# AFE_BQ-Chip.net
KiCad netlist of a schematic drawn in Altium Designer
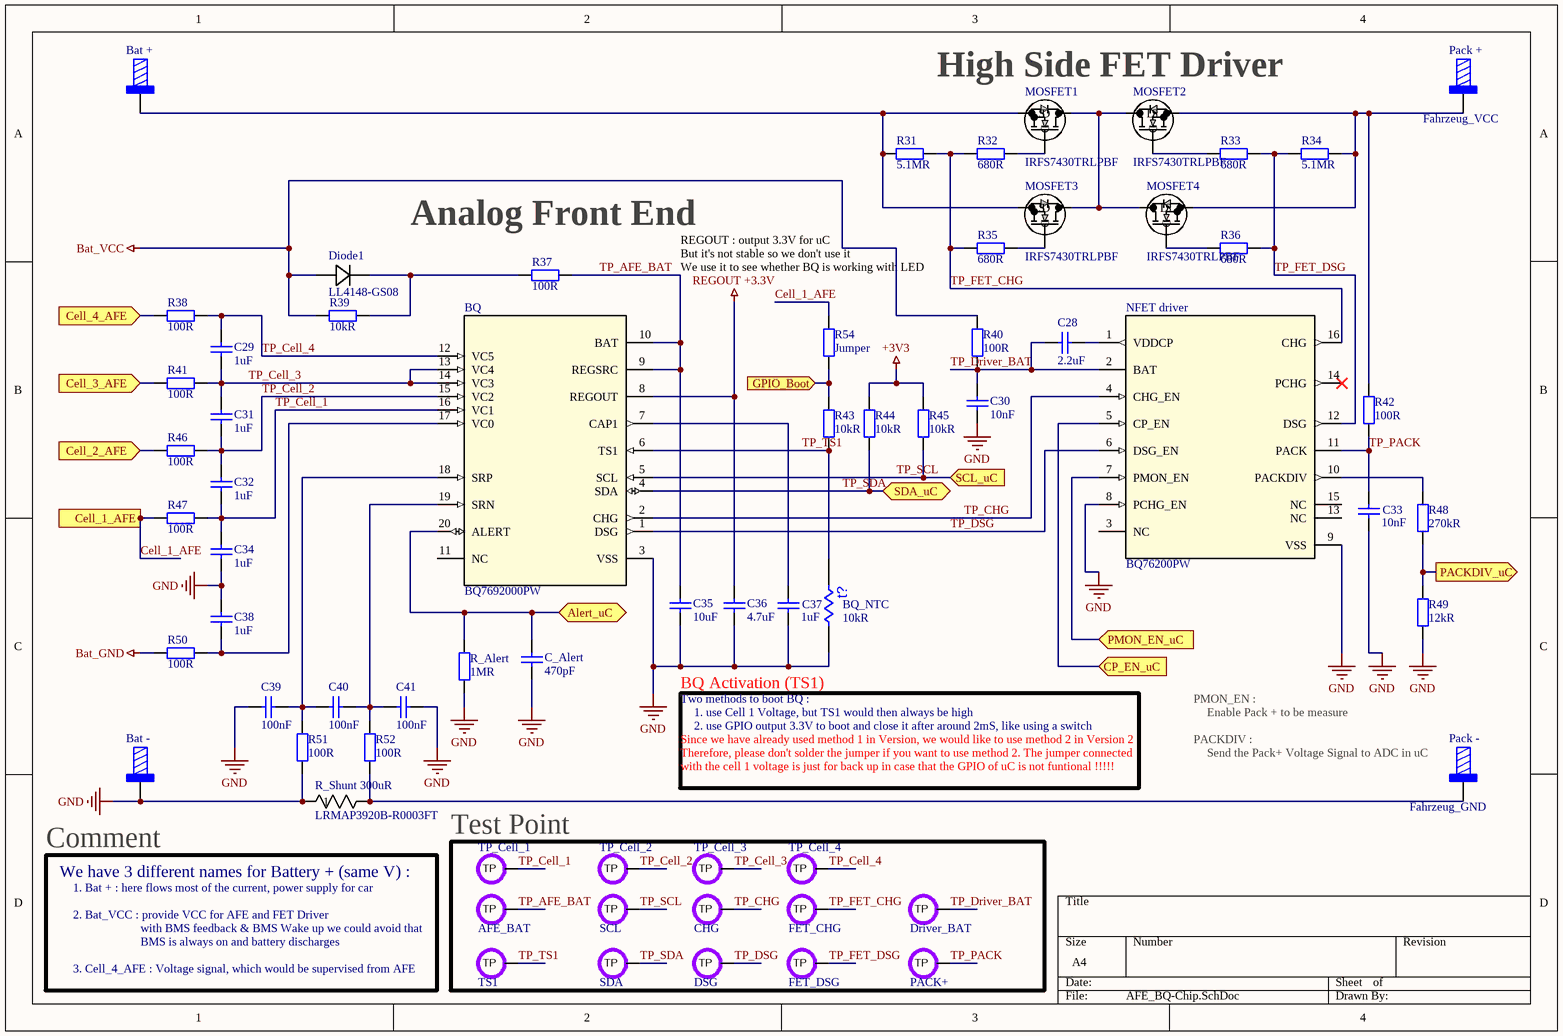
[diagram p0: AFE_BQ-Chip.SchDoc]

(export (version "E")
  (design (tool "Eeschema 10.0.6"))
  (components
    (comp (ref "AFE_BAT")
      (value "TP_1")
      (footprint "Test point")
      (libsource (lib "Schlib1") (part "Test point"))
    )
    (comp (ref "Bat +")
      (value "M4x6mm")
      (footprint "7461096_for chemical surfaces")
      (description "WP-SHFU Press-Fit with External thread, full plain, 7x7mm, 9 pins, M4x6mm, 130A")
      (fields (field (name "PART NUMBER") "7461096") (field (name "PUBLISHER") "Wurth Elektronik"))
      (libsource (lib "GND Pillar") (part "7461096"))
    )
    (comp (ref "Bat -")
      (value "M4x6mm")
      (footprint "7461096_for chemical surfaces")
      (description "WP-SHFU Press-Fit with External thread, full plain, 7x7mm, 9 pins, M4x6mm, 130A")
      (fields (field (name "PART NUMBER") "7461096") (field (name "PUBLISHER") "Wurth Elektronik"))
      (libsource (lib "GND Pillar") (part "7461096"))
    )
    (comp (ref "BQ")
      (value "BQ7692000PW")
      (footprint "PW0020A_N")
      (description "AFE Cell battery monitor")
      (fields
        (field (name "PARTNUMBER") "BQ7692000PWR")
        (field (name "MANUFACTURER") "Texas Instruments")
        (field (name "COPYRIGHT") "Copyright (C) 2018 Accelerated Designs. All rights reserved")
      )
      (libsource (lib "BQ7692000PW") (part "BQ7692000PW"))
    )
    (comp (ref "BQ_NTC")
      (value "10kR")
      (footprint "J1-0603")
      (description "Thermistor")
      (fields (field (name "PUBLISHER") "Altium Limited"))
      (libsource (lib "Miscellaneous Devices") (part "Res Thermal"))
    )
    (comp (ref "C28")
      (value "2.2uF")
      (footprint "1608[0603]")
      (description "Capacitor")
      (fields (field (name "PUBLISHER") "Altium Limited"))
      (libsource (lib "Miscellaneous Devices") (part "Cap"))
    )
    (comp (ref "C29")
      (value "1uF")
      (footprint "1608[0603]")
      (description "Capacitor")
      (fields (field (name "PUBLISHER") "Altium Limited"))
      (libsource (lib "Miscellaneous Devices") (part "Cap"))
    )
    (comp (ref "C30")
      (value "10nF")
      (footprint "1608[0603]")
      (description "Capacitor")
      (fields (field (name "PUBLISHER") "Altium Limited"))
      (libsource (lib "Miscellaneous Devices") (part "Cap"))
    )
    (comp (ref "C31")
      (value "1uF")
      (footprint "1608[0603]")
      (description "Capacitor")
      (fields (field (name "PUBLISHER") "Altium Limited"))
      (libsource (lib "Miscellaneous Devices") (part "Cap"))
    )
    (comp (ref "C32")
      (value "1uF")
      (footprint "1608[0603]")
      (description "Capacitor")
      (fields (field (name "PUBLISHER") "Altium Limited"))
      (libsource (lib "Miscellaneous Devices") (part "Cap"))
    )
    (comp (ref "C33")
      (value "10nF")
      (footprint "1608[0603]")
      (description "Capacitor")
      (fields (field (name "PUBLISHER") "Altium Limited"))
      (libsource (lib "Miscellaneous Devices") (part "Cap"))
    )
    (comp (ref "C34")
      (value "1uF")
      (footprint "1608[0603]")
      (description "Capacitor")
      (fields (field (name "PUBLISHER") "Altium Limited"))
      (libsource (lib "Miscellaneous Devices") (part "Cap"))
    )
    (comp (ref "C35")
      (value "10uF")
      (footprint "1608[0603]")
      (description "Capacitor")
      (fields (field (name "PUBLISHER") "Altium Limited"))
      (libsource (lib "Miscellaneous Devices") (part "Cap"))
    )
    (comp (ref "C36")
      (value "4.7uF")
      (footprint "1608[0603]")
      (description "Capacitor")
      (fields (field (name "PUBLISHER") "Altium Limited"))
      (libsource (lib "Miscellaneous Devices") (part "Cap"))
    )
    (comp (ref "C37")
      (value "1uF")
      (footprint "1608[0603]")
      (description "Capacitor")
      (fields (field (name "PUBLISHER") "Altium Limited"))
      (libsource (lib "Miscellaneous Devices") (part "Cap"))
    )
    (comp (ref "C38")
      (value "1uF")
      (footprint "1608[0603]")
      (description "Capacitor")
      (fields (field (name "PUBLISHER") "Altium Limited"))
      (libsource (lib "Miscellaneous Devices") (part "Cap"))
    )
    (comp (ref "C39")
      (value "100nF")
      (footprint "1608[0603]")
      (description "Capacitor")
      (fields (field (name "PUBLISHER") "Altium Limited"))
      (libsource (lib "Miscellaneous Devices") (part "Cap"))
    )
    (comp (ref "C40")
      (value "100nF")
      (footprint "1608[0603]")
      (description "Capacitor")
      (fields (field (name "PUBLISHER") "Altium Limited"))
      (libsource (lib "Miscellaneous Devices") (part "Cap"))
    )
    (comp (ref "C41")
      (value "100nF")
      (footprint "1608[0603]")
      (description "Capacitor")
      (fields (field (name "PUBLISHER") "Altium Limited"))
      (libsource (lib "Miscellaneous Devices") (part "Cap"))
    )
    (comp (ref "CHG") (value "TP_1") (footprint "Test point") (libsource (lib "Schlib1") (part "Test point")))
    (comp (ref "C_Alert")
      (value "470pF")
      (footprint "1608[0603]")
      (description "Capacitor")
      (fields (field (name "PUBLISHER") "Altium Limited"))
      (libsource (lib "Miscellaneous Devices") (part "Cap"))
    )
    (comp (ref "Diode1")
      (value "LL4148-GS08")
      (footprint "MELF_SOD-80_VIS")
      (description "No Description Available")
      (fields (field (name "COPYRIGHT") "Copyright (C) 2018 Accelerated Designs. All rights reserved"))
      (libsource (lib "Small Signal Switching Diodes") (part "LL4148-GS08"))
    )
    (comp (ref "Driver_BAT")
      (value "TP_1")
      (footprint "Test point")
      (libsource (lib "Schlib1") (part "Test point"))
    )
    (comp (ref "DSG") (value "TP_1") (footprint "Test point") (libsource (lib "Schlib1") (part "Test point")))
    (comp (ref "FET_CHG")
      (value "TP_1")
      (footprint "Test point")
      (libsource (lib "Schlib1") (part "Test point"))
    )
    (comp (ref "FET_DSG")
      (value "TP_1")
      (footprint "Test point")
      (libsource (lib "Schlib1") (part "Test point"))
    )
    (comp (ref "MOSFET1")
      (value "IRFS7430TRLPBF")
      (footprint "D2PAK_TO-263AB_INF-M")
      (description "No Description Available")
      (fields (field (name "COPYRIGHT") "Copyright (C) 2018 Accelerated Designs. All rights reserved"))
      (libsource (lib "Power MOSFET") (part "IRFS7430TRLPBF"))
    )
    (comp (ref "MOSFET2")
      (value "IRFS7430TRLPBF")
      (footprint "D2PAK_TO-263AB_INF-M")
      (description "No Description Available")
      (fields (field (name "COPYRIGHT") "Copyright (C) 2018 Accelerated Designs. All rights reserved"))
      (libsource (lib "Power MOSFET") (part "IRFS7430TRLPBF"))
    )
    (comp (ref "MOSFET3")
      (value "IRFS7430TRLPBF")
      (footprint "D2PAK_TO-263AB_INF-M")
      (description "No Description Available")
      (fields (field (name "COPYRIGHT") "Copyright (C) 2018 Accelerated Designs. All rights reserved"))
      (libsource (lib "Power MOSFET") (part "IRFS7430TRLPBF"))
    )
    (comp (ref "MOSFET4")
      (value "IRFS7430TRLPBF")
      (footprint "D2PAK_TO-263AB_INF-M")
      (description "No Description Available")
      (fields (field (name "COPYRIGHT") "Copyright (C) 2018 Accelerated Designs. All rights reserved"))
      (libsource (lib "Power MOSFET") (part "IRFS7430TRLPBF"))
    )
    (comp (ref "NFET driver")
      (value "BQ76200PW")
      (footprint "PW0016A_L")
      (description "high-side NFET driver")
      (fields
        (field (name "PARTNUMBER") "BQ76200PWR")
        (field (name "MANUFACTURER") "Texas Instruments")
        (field (name "COPYRIGHT") "Copyright (C) 2018 Accelerated Designs. All rights reserved")
      )
      (libsource (lib "BQ76200PW") (part "BQ76200PW"))
    )
    (comp (ref "Pack +")
      (value "Fahrzeug_VCC")
      (footprint "7461096_for chemical surfaces")
      (description "WP-SHFU Press-Fit with External thread, full plain, 7x7mm, 9 pins, M4x6mm, 130A")
      (fields (field (name "PART NUMBER") "7461096") (field (name "PUBLISHER") "Wurth Elektronik"))
      (libsource (lib "GND Pillar") (part "7461096"))
    )
    (comp (ref "Pack -")
      (value "Fahrzeug_GND")
      (footprint "7461096_for chemical surfaces")
      (description "WP-SHFU Press-Fit with External thread, full plain, 7x7mm, 9 pins, M4x6mm, 130A")
      (fields (field (name "PART NUMBER") "7461096") (field (name "PUBLISHER") "Wurth Elektronik"))
      (libsource (lib "GND Pillar") (part "7461096"))
    )
    (comp (ref "PACK+")
      (value "TP_1")
      (footprint "Test point")
      (libsource (lib "Schlib1") (part "Test point"))
    )
    (comp (ref "R31")
      (value "5.1MR")
      (footprint "J1-0603")
      (description "Resistor")
      (fields (field (name "PUBLISHER") "Altium Limited"))
      (libsource (lib "") (part "Res2_3"))
    )
    (comp (ref "R32")
      (value "680R")
      (footprint "J1-0603")
      (description "Resistor")
      (fields (field (name "PUBLISHER") "Altium Limited"))
      (libsource (lib "") (part "Res2_3"))
    )
    (comp (ref "R33")
      (value "680R")
      (footprint "J1-0603")
      (description "Resistor")
      (fields (field (name "PUBLISHER") "Altium Limited"))
      (libsource (lib "") (part "Res2_3"))
    )
    (comp (ref "R34")
      (value "5.1MR")
      (footprint "J1-0603")
      (description "Resistor")
      (fields (field (name "PUBLISHER") "Altium Limited"))
      (libsource (lib "") (part "Res2_3"))
    )
    (comp (ref "R35")
      (value "680R")
      (footprint "J1-0603")
      (description "Resistor")
      (fields (field (name "PUBLISHER") "Altium Limited"))
      (libsource (lib "") (part "Res2_3"))
    )
    (comp (ref "R36")
      (value "680R")
      (footprint "J1-0603")
      (description "Resistor")
      (fields (field (name "PUBLISHER") "Altium Limited"))
      (libsource (lib "") (part "Res2_3"))
    )
    (comp (ref "R37")
      (value "100R")
      (footprint "J1-0603")
      (description "Resistor")
      (fields (field (name "PUBLISHER") "Altium Limited"))
      (libsource (lib "Miscellaneous Devices") (part "Res2"))
    )
    (comp (ref "R38")
      (value "100R")
      (footprint "J1-0603")
      (description "Resistor")
      (fields (field (name "PUBLISHER") "Altium Limited"))
      (libsource (lib "Miscellaneous Devices") (part "Res2"))
    )
    (comp (ref "R39")
      (value "10kR")
      (footprint "J1-0603")
      (description "Resistor")
      (fields (field (name "PUBLISHER") "Altium Limited"))
      (libsource (lib "Miscellaneous Devices") (part "Res2"))
    )
    (comp (ref "R40")
      (value "100R")
      (footprint "J1-0603")
      (description "Resistor")
      (fields (field (name "PUBLISHER") "Altium Limited"))
      (libsource (lib "") (part "Res2_1"))
    )
    (comp (ref "R41")
      (value "100R")
      (footprint "J1-0603")
      (description "Resistor")
      (fields (field (name "PUBLISHER") "Altium Limited"))
      (libsource (lib "Miscellaneous Devices") (part "Res2"))
    )
    (comp (ref "R42")
      (value "100R")
      (footprint "J1-0603")
      (description "Resistor")
      (fields (field (name "PUBLISHER") "Altium Limited"))
      (libsource (lib "") (part "Res2_2"))
    )
    (comp (ref "R43")
      (value "10kR")
      (footprint "J1-0603")
      (description "Resistor")
      (fields (field (name "PUBLISHER") "Altium Limited"))
      (libsource (lib "Miscellaneous Devices") (part "Res2"))
    )
    (comp (ref "R44")
      (value "10kR")
      (footprint "J1-0603")
      (description "Resistor")
      (fields (field (name "PUBLISHER") "Altium Limited"))
      (libsource (lib "") (part "Res2_1"))
    )
    (comp (ref "R45")
      (value "10kR")
      (footprint "J1-0603")
      (description "Resistor")
      (fields (field (name "PUBLISHER") "Altium Limited"))
      (libsource (lib "") (part "Res2_1"))
    )
    (comp (ref "R46")
      (value "100R")
      (footprint "J1-0603")
      (description "Resistor")
      (fields (field (name "PUBLISHER") "Altium Limited"))
      (libsource (lib "Miscellaneous Devices") (part "Res2"))
    )
    (comp (ref "R47")
      (value "100R")
      (footprint "J1-0603")
      (description "Resistor")
      (fields (field (name "PUBLISHER") "Altium Limited"))
      (libsource (lib "Miscellaneous Devices") (part "Res2"))
    )
    (comp (ref "R48")
      (value "270kR")
      (footprint "J1-0603")
      (description "Resistor")
      (fields (field (name "PUBLISHER") "Altium Limited"))
      (libsource (lib "") (part "Res2_2"))
    )
    (comp (ref "R49")
      (value "12kR")
      (footprint "J1-0603")
      (description "Resistor")
      (fields (field (name "PUBLISHER") "Altium Limited"))
      (libsource (lib "") (part "Res2_2"))
    )
    (comp (ref "R50")
      (value "100R")
      (footprint "J1-0603")
      (description "Resistor")
      (fields (field (name "PUBLISHER") "Altium Limited"))
      (libsource (lib "") (part "Res2_1"))
    )
    (comp (ref "R51")
      (value "100R")
      (footprint "J1-0603")
      (description "Resistor")
      (fields (field (name "PUBLISHER") "Altium Limited"))
      (libsource (lib "Miscellaneous Devices") (part "Res2"))
    )
    (comp (ref "R52")
      (value "100R")
      (footprint "J1-0603")
      (description "Resistor")
      (fields (field (name "PUBLISHER") "Altium Limited"))
      (libsource (lib "Miscellaneous Devices") (part "Res2"))
    )
    (comp (ref "R54")
      (value "Jumper")
      (footprint "J1-0603")
      (description "Resistor")
      (fields (field (name "PUBLISHER") "Altium Limited"))
      (libsource (lib "") (part "Res2_2"))
    )
    (comp (ref "R_Alert")
      (value "1MR")
      (footprint "J1-0603")
      (description "Resistor")
      (fields (field (name "PUBLISHER") "Altium Limited"))
      (libsource (lib "Miscellaneous Devices") (part "Res2"))
    )
    (comp (ref "R_Shunt 300uR")
      (value "LRMAP3920B-R0003FT")
      (footprint "RES_LRMAP3920B-R0003FT_WEL")
      (description "No Description Available")
      (fields (field (name "COPYRIGHT") "Copyright (C) 2018 Accelerated Designs. All rights reserved"))
      (libsource (lib "Shunt R") (part "LRMAP3920B-R0003FT"))
    )
    (comp (ref "SCL") (value "TP_1") (footprint "Test point") (libsource (lib "Schlib1") (part "Test point")))
    (comp (ref "SDA") (value "TP_1") (footprint "Test point") (libsource (lib "Schlib1") (part "Test point")))
    (comp (ref "TP_Cell_1")
      (value "TP_1")
      (footprint "Test point")
      (libsource (lib "Schlib1") (part "Test point"))
    )
    (comp (ref "TP_Cell_2")
      (value "TP_1")
      (footprint "Test point")
      (libsource (lib "Schlib1") (part "Test point"))
    )
    (comp (ref "TP_Cell_3")
      (value "TP_1")
      (footprint "Test point")
      (libsource (lib "Schlib1") (part "Test point"))
    )
    (comp (ref "TP_Cell_4")
      (value "TP_1")
      (footprint "Test point")
      (libsource (lib "Schlib1") (part "Test point"))
    )
    (comp (ref "TS1") (value "TP_1") (footprint "Test point") (libsource (lib "Schlib1") (part "Test point")))
  )
  (nets
    (net (code "1") (name "+3V3") (class "Default")
      (node (ref "R44") (pin "1") (pinfunction "1_1") (pintype "passive"))
      (node (ref "R45") (pin "1") (pinfunction "1_1") (pintype "passive"))
    )
    (net (code "2") (name "/Alert_uC") (class "Default")
      (node (ref "BQ") (pin "20") (pinfunction "ALERT_20") (pintype "bidirectional"))
      (node (ref "C_Alert") (pin "1") (pinfunction "1_1") (pintype "passive"))
      (node (ref "R_Alert") (pin "1") (pinfunction "1_1") (pintype "passive"))
    )
    (net (code "3") (name "/CP_EN_uC") (class "Default")
      (node (ref "NFET driver") (pin "5") (pinfunction "CP_EN_5") (pintype "input"))
    )
    (net (code "4") (name "/Cell_1_AFE") (class "Default")
      (node (ref "R47") (pin "2") (pinfunction "2_2") (pintype "passive"))
      (node (ref "R54") (pin "2") (pinfunction "2_2") (pintype "passive"))
    )
    (net (code "5") (name "/Cell_2_AFE") (class "Default")
      (node (ref "R46") (pin "2") (pinfunction "2_2") (pintype "passive"))
    )
    (net (code "6") (name "/Cell_3_AFE") (class "Default")
      (node (ref "R41") (pin "2") (pinfunction "2_2") (pintype "passive"))
    )
    (net (code "7") (name "/Cell_4_AFE") (class "Default")
      (node (ref "R38") (pin "2") (pinfunction "2_2") (pintype "passive"))
    )
    (net (code "8") (name "/GPIO_Boot") (class "Default")
      (node (ref "R43") (pin "1") (pinfunction "1_1") (pintype "passive"))
      (node (ref "R54") (pin "1") (pinfunction "1_1") (pintype "passive"))
    )
    (net (code "9") (name "/PACKDIV_uC") (class "Default")
      (node (ref "R48") (pin "1") (pinfunction "1_1") (pintype "passive"))
      (node (ref "R49") (pin "2") (pinfunction "2_2") (pintype "passive"))
    )
    (net (code "10") (name "/PMON_EN_uC") (class "Default")
      (node (ref "NFET driver") (pin "7") (pinfunction "PMON_EN_7") (pintype "input"))
    )
    (net (code "11") (name "/TP_AFE_BAT") (class "Default")
      (node (ref "AFE_BAT") (pin "1") (pinfunction "TP_1") (pintype "passive"))
      (node (ref "BQ") (pin "10") (pinfunction "BAT_10") (pintype "power_in"))
      (node (ref "BQ") (pin "9") (pinfunction "REGSRC_9") (pintype "power_in"))
      (node (ref "C35") (pin "1") (pinfunction "1_1") (pintype "passive"))
      (node (ref "R37") (pin "1") (pinfunction "1_1") (pintype "passive"))
    )
    (net (code "12") (name "/TP_CHG") (class "Default")
      (node (ref "BQ") (pin "2") (pinfunction "CHG_2") (pintype "output"))
      (node (ref "CHG") (pin "1") (pinfunction "TP_1") (pintype "passive"))
      (node (ref "NFET driver") (pin "4") (pinfunction "CHG_EN_4") (pintype "input"))
    )
    (net (code "13") (name "/TP_Cell_1") (class "Default")
      (node (ref "BQ") (pin "16") (pinfunction "VC1_16") (pintype "input"))
      (node (ref "C32") (pin "1") (pinfunction "1_1") (pintype "passive"))
      (node (ref "C34") (pin "2") (pinfunction "2_2") (pintype "passive"))
      (node (ref "R47") (pin "1") (pinfunction "1_1") (pintype "passive"))
      (node (ref "TP_Cell_1") (pin "1") (pinfunction "TP_1") (pintype "passive"))
    )
    (net (code "14") (name "/TP_Cell_2") (class "Default")
      (node (ref "BQ") (pin "15") (pinfunction "VC2_15") (pintype "input"))
      (node (ref "C31") (pin "1") (pinfunction "1_1") (pintype "passive"))
      (node (ref "C32") (pin "2") (pinfunction "2_2") (pintype "passive"))
      (node (ref "R46") (pin "1") (pinfunction "1_1") (pintype "passive"))
      (node (ref "TP_Cell_2") (pin "1") (pinfunction "TP_1") (pintype "passive"))
    )
    (net (code "15") (name "/TP_Cell_3") (class "Default")
      (node (ref "BQ") (pin "13") (pinfunction "VC4_13") (pintype "input"))
      (node (ref "BQ") (pin "14") (pinfunction "VC3_14") (pintype "input"))
      (node (ref "C29") (pin "1") (pinfunction "1_1") (pintype "passive"))
      (node (ref "C31") (pin "2") (pinfunction "2_2") (pintype "passive"))
      (node (ref "R41") (pin "1") (pinfunction "1_1") (pintype "passive"))
      (node (ref "TP_Cell_3") (pin "1") (pinfunction "TP_1") (pintype "passive"))
    )
    (net (code "16") (name "/TP_Cell_4") (class "Default")
      (node (ref "BQ") (pin "12") (pinfunction "VC5_12") (pintype "input"))
      (node (ref "C29") (pin "2") (pinfunction "2_2") (pintype "passive"))
      (node (ref "R38") (pin "1") (pinfunction "1_1") (pintype "passive"))
      (node (ref "TP_Cell_4") (pin "1") (pinfunction "TP_1") (pintype "passive"))
    )
    (net (code "17") (name "/TP_DSG") (class "Default")
      (node (ref "BQ") (pin "1") (pinfunction "DSG_1") (pintype "output"))
      (node (ref "DSG") (pin "1") (pinfunction "TP_1") (pintype "passive"))
      (node (ref "NFET driver") (pin "6") (pinfunction "DSG_EN_6") (pintype "input"))
    )
    (net (code "18") (name "/TP_Driver_BAT") (class "Default")
      (node (ref "C28") (pin "2") (pinfunction "2_2") (pintype "passive"))
      (node (ref "C30") (pin "2") (pinfunction "2_2") (pintype "passive"))
      (node (ref "Driver_BAT") (pin "1") (pinfunction "TP_1") (pintype "passive"))
      (node (ref "NFET driver") (pin "2") (pinfunction "BAT_2") (pintype "power_in"))
      (node (ref "R40") (pin "2") (pinfunction "2_2") (pintype "passive"))
    )
    (net (code "19") (name "/TP_FET_CHG") (class "Default")
      (node (ref "FET_CHG") (pin "1") (pinfunction "TP_1") (pintype "passive"))
      (node (ref "NFET driver") (pin "16") (pinfunction "CHG_16") (pintype "output"))
      (node (ref "R31") (pin "2") (pinfunction "2_2") (pintype "passive"))
      (node (ref "R32") (pin "1") (pinfunction "1_1") (pintype "passive"))
      (node (ref "R35") (pin "1") (pinfunction "1_1") (pintype "passive"))
    )
    (net (code "20") (name "/TP_FET_DSG") (class "Default")
      (node (ref "FET_DSG") (pin "1") (pinfunction "TP_1") (pintype "passive"))
      (node (ref "NFET driver") (pin "12") (pinfunction "DSG_12") (pintype "output"))
      (node (ref "R33") (pin "2") (pinfunction "2_2") (pintype "passive"))
      (node (ref "R34") (pin "1") (pinfunction "1_1") (pintype "passive"))
      (node (ref "R36") (pin "2") (pinfunction "2_2") (pintype "passive"))
    )
    (net (code "21") (name "/TP_PACK") (class "Default")
      (node (ref "C33") (pin "1") (pinfunction "1_1") (pintype "passive"))
      (node (ref "NFET driver") (pin "11") (pinfunction "PACK_11") (pintype "power_in"))
      (node (ref "PACK+") (pin "1") (pinfunction "TP_1") (pintype "passive"))
      (node (ref "R42") (pin "1") (pinfunction "1_1") (pintype "passive"))
    )
    (net (code "22") (name "/TP_SCL") (class "Default")
      (node (ref "BQ") (pin "5") (pinfunction "SCL_5") (pintype "input"))
      (node (ref "R45") (pin "2") (pinfunction "2_2") (pintype "passive"))
      (node (ref "SCL") (pin "1") (pinfunction "TP_1") (pintype "passive"))
    )
    (net (code "23") (name "/TP_SDA") (class "Default")
      (node (ref "BQ") (pin "4") (pinfunction "SDA_4") (pintype "bidirectional"))
      (node (ref "R44") (pin "2") (pinfunction "2_2") (pintype "passive"))
      (node (ref "SDA") (pin "1") (pinfunction "TP_1") (pintype "passive"))
    )
    (net (code "24") (name "/TP_TS1") (class "Default")
      (node (ref "BQ") (pin "6") (pinfunction "TS1_6") (pintype "input"))
      (node (ref "BQ_NTC") (pin "1") (pinfunction "1_1") (pintype "passive"))
      (node (ref "R43") (pin "2") (pinfunction "2_2") (pintype "passive"))
      (node (ref "TS1") (pin "1") (pinfunction "TP_1") (pintype "passive"))
    )
    (net (code "25") (name "Bat_GND") (class "Default")
      (node (ref "R50") (pin "2") (pinfunction "2_2") (pintype "passive"))
    )
    (net (code "26") (name "Bat_VCC") (class "Default")
      (node (ref "Diode1") (pin "2") (pinfunction "2_2") (pintype "passive"))
      (node (ref "R39") (pin "2") (pinfunction "2_2") (pintype "passive"))
      (node (ref "R40") (pin "1") (pinfunction "1_1") (pintype "passive"))
    )
    (net (code "27") (name "GND") (class "Default")
      (node (ref "BQ") (pin "3") (pinfunction "VSS_3") (pintype "power_in"))
      (node (ref "BQ_NTC") (pin "2") (pinfunction "2_2") (pintype "passive"))
      (node (ref "Bat -") (pin "1") (pinfunction "1_1") (pintype "passive"))
      (node (ref "C30") (pin "1") (pinfunction "1_1") (pintype "passive"))
      (node (ref "C33") (pin "2") (pinfunction "2_2") (pintype "passive"))
      (node (ref "C34") (pin "1") (pinfunction "1_1") (pintype "passive"))
      (node (ref "C35") (pin "2") (pinfunction "2_2") (pintype "passive"))
      (node (ref "C36") (pin "2") (pinfunction "2_2") (pintype "passive"))
      (node (ref "C37") (pin "2") (pinfunction "2_2") (pintype "passive"))
      (node (ref "C38") (pin "1") (pinfunction "1_1") (pintype "passive"))
      (node (ref "C39") (pin "2") (pinfunction "2_2") (pintype "passive"))
      (node (ref "C41") (pin "1") (pinfunction "1_1") (pintype "passive"))
      (node (ref "C_Alert") (pin "2") (pinfunction "2_2") (pintype "passive"))
      (node (ref "NFET driver") (pin "8") (pinfunction "PCHG_EN_8") (pintype "input"))
      (node (ref "NFET driver") (pin "9") (pinfunction "VSS_9") (pintype "power_in"))
      (node (ref "R49") (pin "1") (pinfunction "1_1") (pintype "passive"))
      (node (ref "R51") (pin "2") (pinfunction "2_2") (pintype "passive"))
      (node (ref "R_Alert") (pin "2") (pinfunction "2_2") (pintype "passive"))
      (node (ref "R_Shunt 300uR") (pin "1") (pinfunction "1_1") (pintype "passive"))
    )
    (net (code "28") (name "Net-(BQ-CAP1)") (class "Default")
      (node (ref "BQ") (pin "7") (pinfunction "CAP1_7") (pintype "output"))
      (node (ref "C37") (pin "1") (pinfunction "1_1") (pintype "passive"))
    )
    (net (code "29") (name "Net-(BQ-SRN)") (class "Default")
      (node (ref "BQ") (pin "19") (pinfunction "SRN_19") (pintype "input"))
      (node (ref "C40") (pin "1") (pinfunction "1_1") (pintype "passive"))
      (node (ref "C41") (pin "2") (pinfunction "2_2") (pintype "passive"))
      (node (ref "R52") (pin "1") (pinfunction "1_1") (pintype "passive"))
    )
    (net (code "30") (name "Net-(BQ-SRP)") (class "Default")
      (node (ref "BQ") (pin "18") (pinfunction "SRP_18") (pintype "input"))
      (node (ref "C39") (pin "1") (pinfunction "1_1") (pintype "passive"))
      (node (ref "C40") (pin "2") (pinfunction "2_2") (pintype "passive"))
      (node (ref "R51") (pin "1") (pinfunction "1_1") (pintype "passive"))
    )
    (net (code "31") (name "Net-(BQ-VC0)") (class "Default")
      (node (ref "BQ") (pin "17") (pinfunction "VC0_17") (pintype "input"))
      (node (ref "C38") (pin "2") (pinfunction "2_2") (pintype "passive"))
      (node (ref "R50") (pin "1") (pinfunction "1_1") (pintype "passive"))
    )
    (net (code "32") (name "Net-(Diode1-Pad1)") (class "Default")
      (node (ref "Diode1") (pin "1") (pinfunction "1_1") (pintype "passive"))
      (node (ref "R37") (pin "2") (pinfunction "2_2") (pintype "passive"))
      (node (ref "R39") (pin "1") (pinfunction "1_1") (pintype "passive"))
    )
    (net (code "33") (name "Net-(MOSFET1-D)") (class "Default")
      (node (ref "MOSFET1") (pin "2") (pinfunction "D_2") (pintype "passive"))
      (node (ref "MOSFET2") (pin "2") (pinfunction "D_2") (pintype "passive"))
      (node (ref "MOSFET3") (pin "2") (pinfunction "D_2") (pintype "passive"))
      (node (ref "MOSFET4") (pin "2") (pinfunction "D_2") (pintype "passive"))
    )
    (net (code "34") (name "Net-(MOSFET1-G)") (class "Default")
      (node (ref "MOSFET1") (pin "1") (pinfunction "G_1") (pintype "passive"))
      (node (ref "R32") (pin "2") (pinfunction "2_2") (pintype "passive"))
    )
    (net (code "35") (name "Net-(MOSFET1-S)") (class "Default")
      (node (ref "Bat +") (pin "1") (pinfunction "1_1") (pintype "passive"))
      (node (ref "MOSFET1") (pin "3") (pinfunction "S_3") (pintype "passive"))
      (node (ref "MOSFET3") (pin "3") (pinfunction "S_3") (pintype "passive"))
      (node (ref "R31") (pin "1") (pinfunction "1_1") (pintype "passive"))
    )
    (net (code "36") (name "Net-(MOSFET2-G)") (class "Default")
      (node (ref "MOSFET2") (pin "1") (pinfunction "G_1") (pintype "passive"))
      (node (ref "R33") (pin "1") (pinfunction "1_1") (pintype "passive"))
    )
    (net (code "37") (name "Net-(MOSFET2-S)") (class "Default")
      (node (ref "MOSFET2") (pin "3") (pinfunction "S_3") (pintype "passive"))
      (node (ref "MOSFET4") (pin "3") (pinfunction "S_3") (pintype "passive"))
      (node (ref "Pack +") (pin "1") (pinfunction "1_1") (pintype "passive"))
      (node (ref "R34") (pin "2") (pinfunction "2_2") (pintype "passive"))
      (node (ref "R42") (pin "2") (pinfunction "2_2") (pintype "passive"))
    )
    (net (code "38") (name "Net-(MOSFET3-G)") (class "Default")
      (node (ref "MOSFET3") (pin "1") (pinfunction "G_1") (pintype "passive"))
      (node (ref "R35") (pin "2") (pinfunction "2_2") (pintype "passive"))
    )
    (net (code "39") (name "Net-(MOSFET4-G)") (class "Default")
      (node (ref "MOSFET4") (pin "1") (pinfunction "G_1") (pintype "passive"))
      (node (ref "R36") (pin "1") (pinfunction "1_1") (pintype "passive"))
    )
    (net (code "40") (name "Net-(NFET driver-PACKDIV)") (class "Default")
      (node (ref "NFET driver") (pin "10") (pinfunction "PACKDIV_10") (pintype "output"))
      (node (ref "R48") (pin "2") (pinfunction "2_2") (pintype "passive"))
    )
    (net (code "41") (name "Net-(NFET driver-VDDCP)") (class "Default")
      (node (ref "C28") (pin "1") (pinfunction "1_1") (pintype "passive"))
      (node (ref "NFET driver") (pin "1") (pinfunction "VDDCP_1") (pintype "output"))
    )
    (net (code "42") (name "Net-(Pack --Pad1)") (class "Default")
      (node (ref "Pack -") (pin "1") (pinfunction "1_1") (pintype "passive"))
      (node (ref "R52") (pin "2") (pinfunction "2_2") (pintype "passive"))
      (node (ref "R_Shunt 300uR") (pin "2") (pinfunction "2_2") (pintype "passive"))
    )
    (net (code "43") (name "REGOUT +3.3V") (class "Default")
      (node (ref "BQ") (pin "8") (pinfunction "REGOUT_8") (pintype "power_in"))
      (node (ref "C36") (pin "1") (pinfunction "1_1") (pintype "passive"))
    )
    (net (code "44") (name "unconnected-(BQ-NC-Pad11)") (class "Default")
      (node (ref "BQ") (pin "11") (pinfunction "NC_11") (pintype "passive"))
    )
    (net (code "45") (name "unconnected-(NFET driver-NC-Pad3)") (class "Default")
      (node (ref "NFET driver") (pin "3") (pinfunction "NC_3") (pintype "passive"))
    )
    (net (code "46") (name "unconnected-(NFET driver-NC-Pad13)") (class "Default")
      (node (ref "NFET driver") (pin "13") (pinfunction "NC_13") (pintype "passive"))
    )
    (net (code "47") (name "unconnected-(NFET driver-NC-Pad15)") (class "Default")
      (node (ref "NFET driver") (pin "15") (pinfunction "NC_15") (pintype "passive"))
    )
    (net (code "48") (name "unconnected-(NFET driver-PCHG-Pad14)") (class "Default")
      (node (ref "NFET driver") (pin "14") (pinfunction "PCHG_14") (pintype "output+no_connect"))
    )
  )
)
